# Zapper.net
KiCad netlist of a schematic drawn in Altium Designer
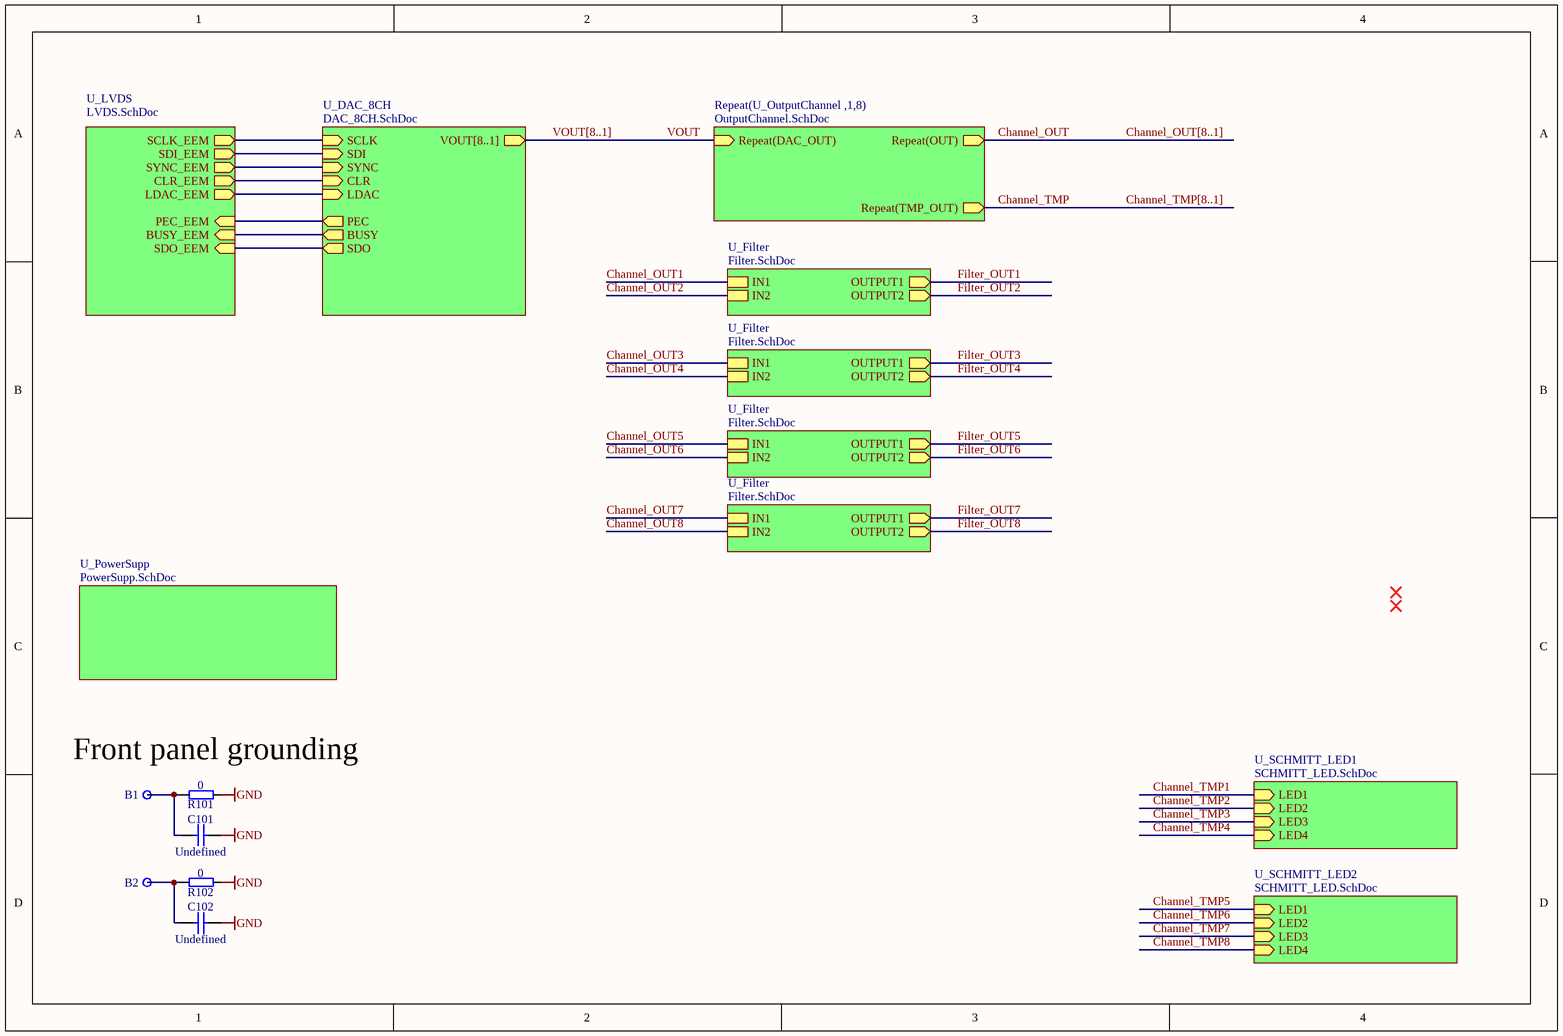
[diagram p0: Zapper.SchDoc]

(export (version "E")
  (design (tool "Eeschema 10.0.6"))
  (components
    (comp (ref "B1")
      (value "Plated Hole")
      (footprint "MTG270_500")
      (description "Single Terminal Socket")
      (fields (field (name "PART NUMBER") "PLATED_HOLE2.7_PAD5.0") (field (name "AUTHOR") "CERN DEM JMW"))
      (libsource (lib "Eletro-mechanical") (part "Single Terminal Socket"))
    )
    (comp (ref "B2")
      (value "Plated Hole")
      (footprint "MTG270_500")
      (description "Single Terminal Socket")
      (fields (field (name "PART NUMBER") "PLATED_HOLE2.7_PAD5.0") (field (name "AUTHOR") "CERN DEM JMW"))
      (libsource (lib "Eletro-mechanical") (part "Single Terminal Socket"))
    )
    (comp (ref "C101")
      (value "Undefined")
      (footprint "CAPC2012X135N")
      (description "Non-polarised capacitor")
      (fields (field (name "PART NUMBER") "CC0805_NO-VALUE") (field (name "AUTHOR") "CERN DEM JLC"))
      (libsource (lib "Capacitors") (part "Capacitor - non polarized"))
    )
    (comp (ref "C102")
      (value "Undefined")
      (footprint "CAPC2012X135N")
      (description "Non-polarised capacitor")
      (fields (field (name "PART NUMBER") "CC0805_NO-VALUE") (field (name "AUTHOR") "CERN DEM JLC"))
      (libsource (lib "Capacitors") (part "Capacitor - non polarized"))
    )
    (comp (ref "R101")
      (value "0")
      (footprint "RESC1608X55N")
      (description "Resistor")
      (fields
        (field (name "PART NUMBER") "R0603_0R_JUMPER")
        (field (name "MANUFACTURER") "GENERIC")
        (field (name "AUTHOR") "CERN DEM JLC")
      )
      (libsource (lib "Resistors") (part "Resistor"))
    )
    (comp (ref "R102")
      (value "0")
      (footprint "RESC1608X55N")
      (description "Resistor")
      (fields
        (field (name "PART NUMBER") "R0603_0R_JUMPER")
        (field (name "MANUFACTURER") "GENERIC")
        (field (name "AUTHOR") "CERN DEM JLC")
      )
      (libsource (lib "Resistors") (part "Resistor"))
    )
  )
  (nets
    (net (code "47") (name "GND") (class "Default")
      (node (ref "C101") (pin "2") (pinfunction "2_2") (pintype "passive"))
      (node (ref "C102") (pin "2") (pinfunction "2_2") (pintype "passive"))
      (node (ref "R101") (pin "1") (pinfunction "1_1") (pintype "passive"))
      (node (ref "R102") (pin "1") (pinfunction "1_1") (pintype "passive"))
    )
    (net (code "48") (name "Net-(B1-Pad1)") (class "Default")
      (node (ref "B1") (pin "1") (pinfunction "1_1") (pintype "bidirectional"))
      (node (ref "C101") (pin "1") (pinfunction "1_1") (pintype "passive"))
      (node (ref "R101") (pin "2") (pinfunction "2_2") (pintype "passive"))
    )
    (net (code "49") (name "Net-(B2-Pad1)") (class "Default")
      (node (ref "B2") (pin "1") (pinfunction "1_1") (pintype "bidirectional"))
      (node (ref "C102") (pin "1") (pinfunction "1_1") (pintype "passive"))
      (node (ref "R102") (pin "2") (pinfunction "2_2") (pintype "passive"))
    )
  )
)
